# KMO_IO_MV2.net
KiCad netlist of a schematic drawn in EAGLE
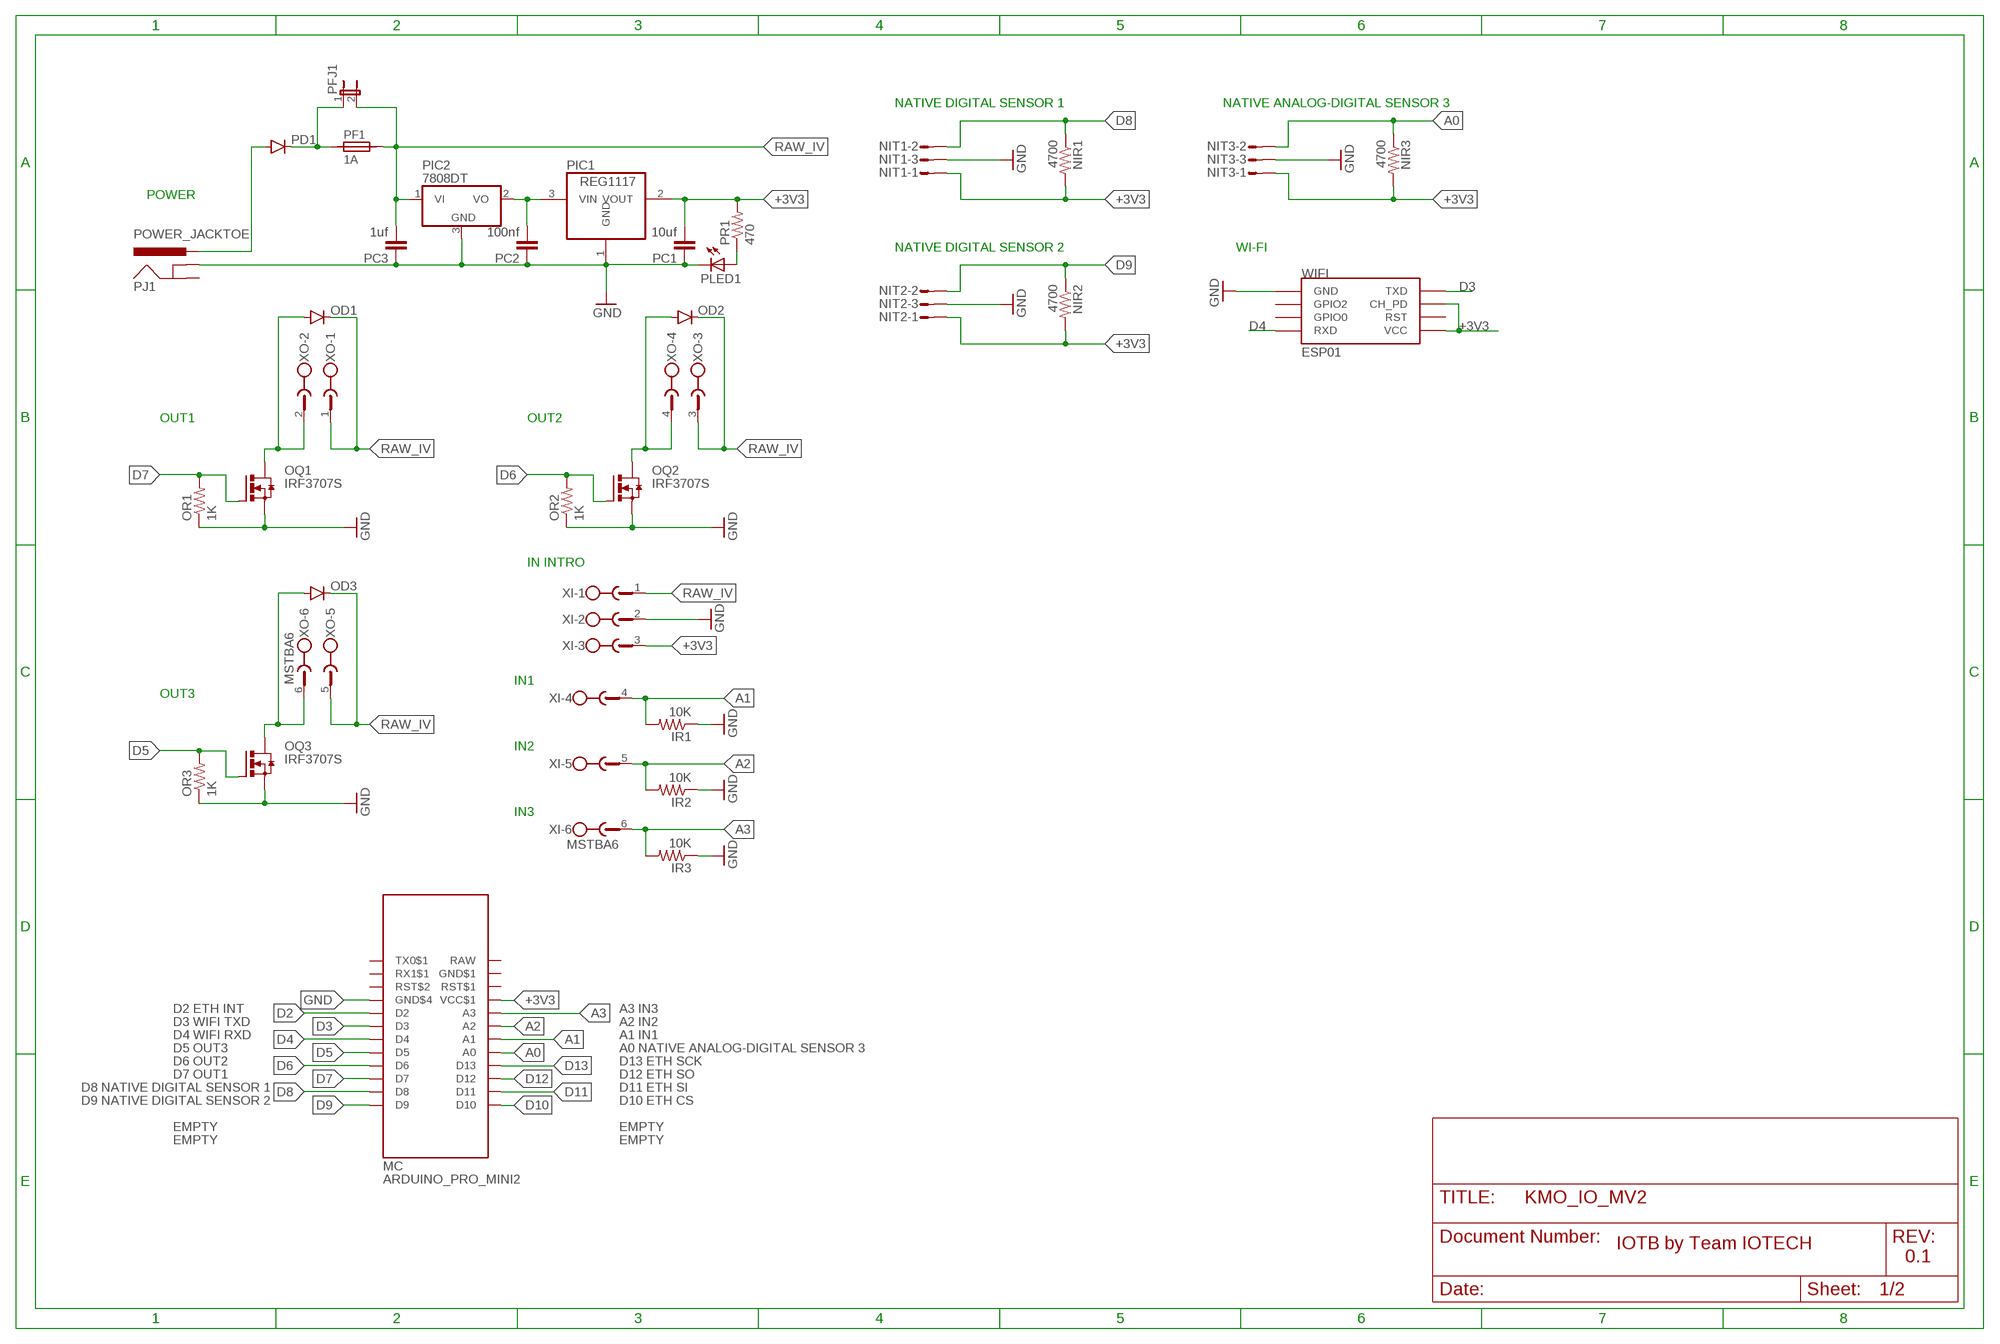
[diagram p0: schematic, sheet 1]
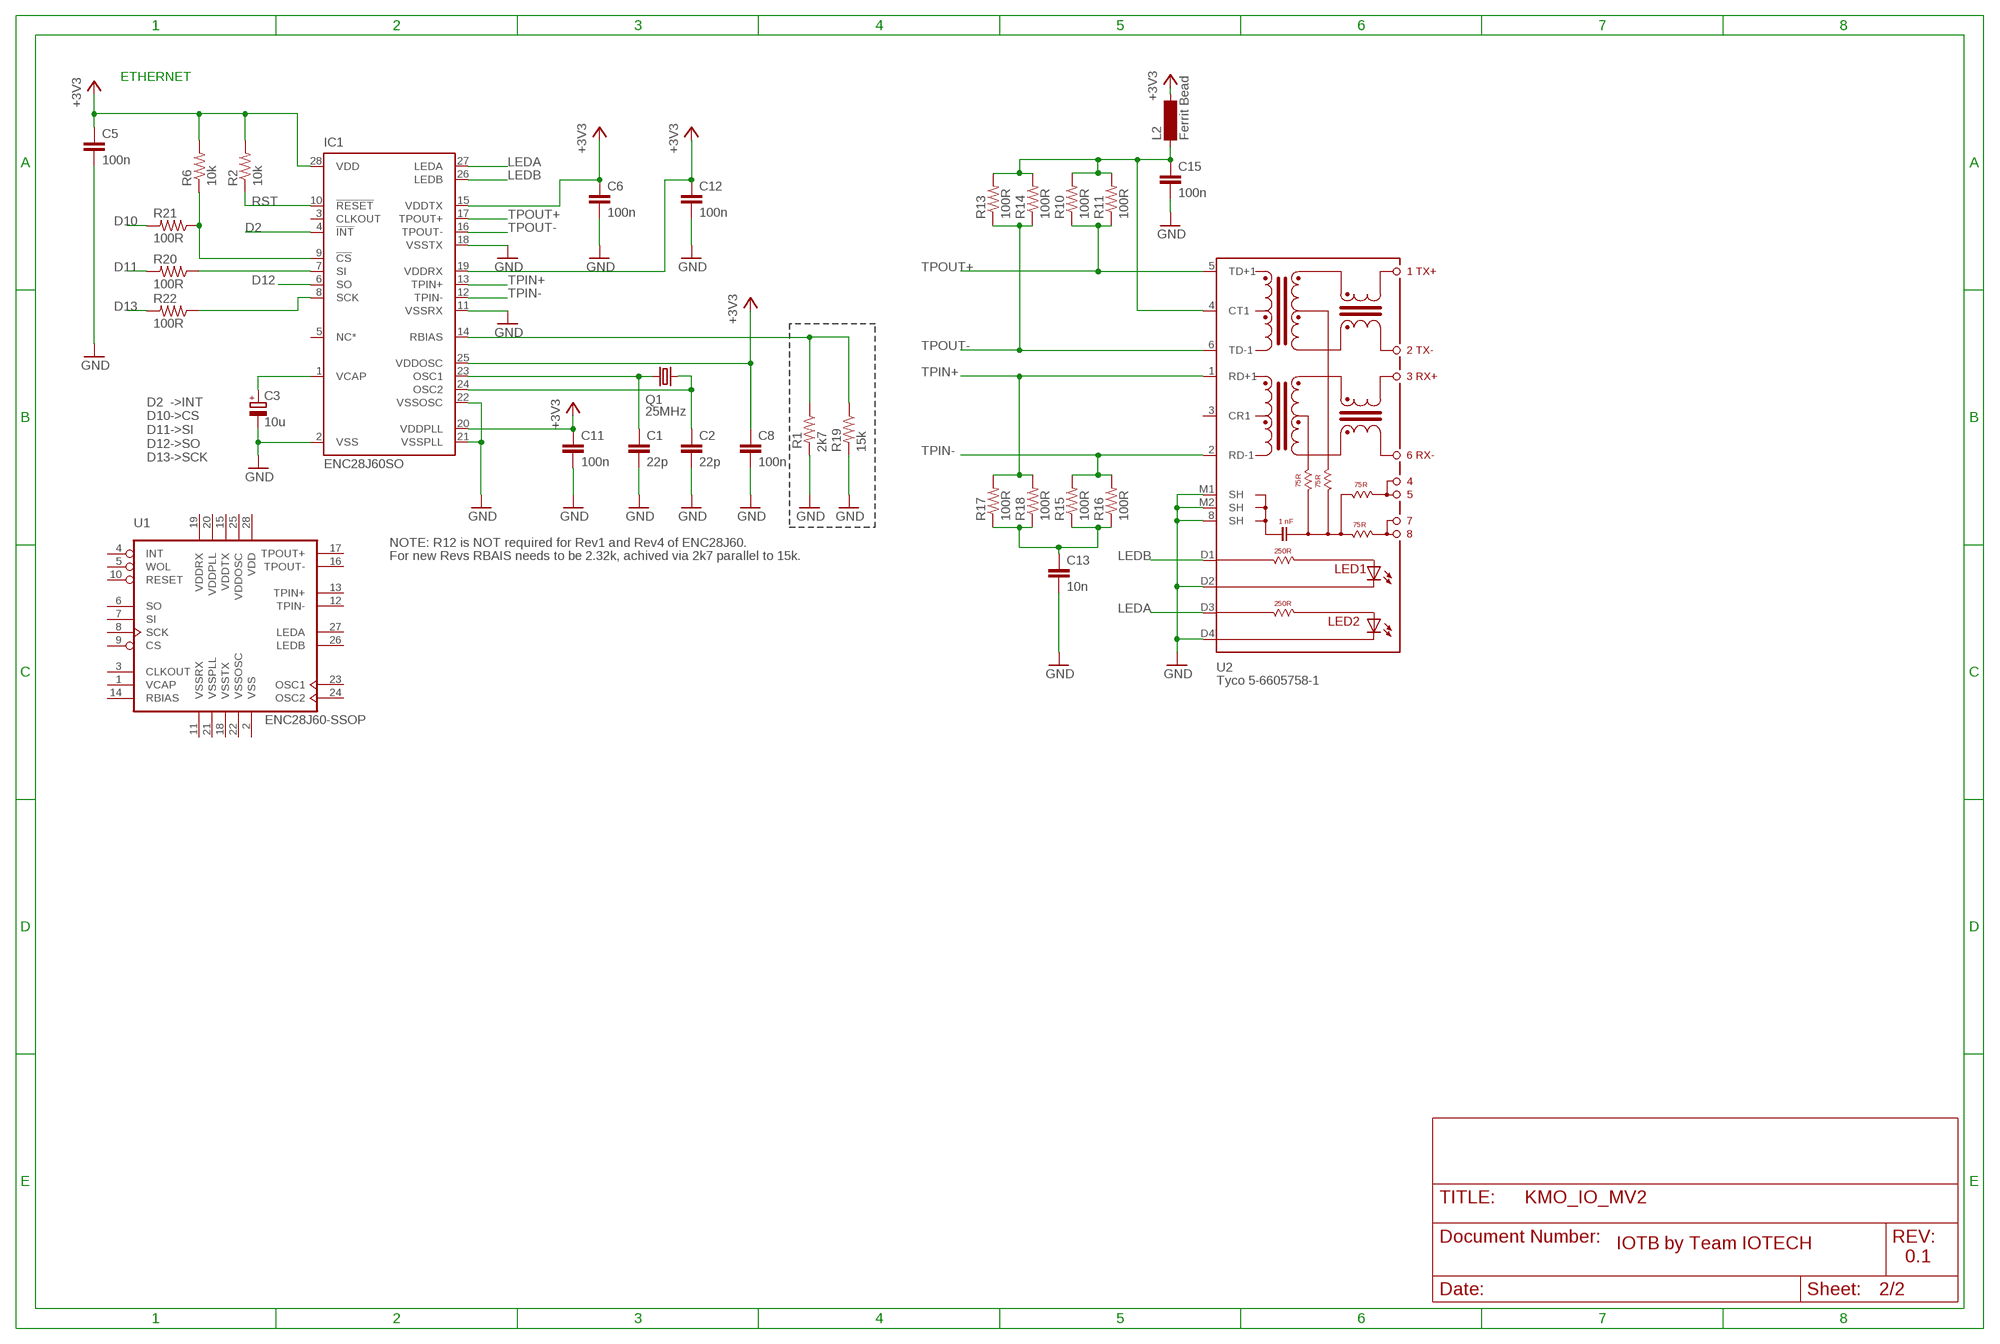
[diagram p1: schematic, sheet 2]

(export (version "E")
  (design (tool "Eeschema 10.0.6"))
  (components
    (comp (ref "C1")
      (value "22p")
      (footprint "eagle-import:0805")
      (libsource (lib "eagle-import") (part "SparkFun-Passives_CAP0805"))
    )
    (comp (ref "C2")
      (value "22p")
      (footprint "eagle-import:0805")
      (libsource (lib "eagle-import") (part "SparkFun-Passives_CAP0805"))
    )
    (comp (ref "C3")
      (value "10u")
      (footprint "eagle-import:E2,5-5")
      (libsource (lib "eagle-import") (part "CPOL-EUE2.5-5"))
    )
    (comp (ref "C5")
      (value "100n")
      (footprint "eagle-import:0805")
      (libsource (lib "eagle-import") (part "SparkFun-Passives_CAP0805"))
    )
    (comp (ref "C6")
      (value "100n")
      (footprint "eagle-import:0805")
      (libsource (lib "eagle-import") (part "SparkFun-Passives_CAP0805"))
    )
    (comp (ref "C8")
      (value "100n")
      (footprint "eagle-import:0805")
      (libsource (lib "eagle-import") (part "SparkFun-Passives_CAP0805"))
    )
    (comp (ref "C11")
      (value "100n")
      (footprint "eagle-import:0805")
      (libsource (lib "eagle-import") (part "SparkFun-Passives_CAP0805"))
    )
    (comp (ref "C12")
      (value "100n")
      (footprint "eagle-import:0805")
      (libsource (lib "eagle-import") (part "SparkFun-Passives_CAP0805"))
    )
    (comp (ref "C13")
      (value "10n")
      (footprint "eagle-import:0805")
      (libsource (lib "eagle-import") (part "SparkFun-Passives_CAP0805"))
    )
    (comp (ref "C15")
      (value "100n")
      (footprint "eagle-import:0805")
      (libsource (lib "eagle-import") (part "SparkFun-Passives_CAP0805"))
    )
    (comp (ref "IC1")
      (value "ENC28J60SO")
      (footprint "eagle-import:SO28W")
      (libsource (lib "eagle-import") (part "ENC28J60SO"))
    )
    (comp (ref "L2")
      (value "Ferrit Bead")
      (footprint "eagle-import:SM-1206")
      (libsource (lib "eagle-import") (part "SM-1206"))
    )
    (comp (ref "Q1")
      (value "25MHz")
      (footprint "eagle-import:HC49_S")
      (libsource (lib "eagle-import") (part "CRYSTALHC49S"))
    )
    (comp (ref "R1")
      (value "2k7")
      (footprint "eagle-import:0805")
      (libsource (lib "eagle-import") (part "RESISTOR0805-RES"))
    )
    (comp (ref "R2")
      (value "10k")
      (footprint "eagle-import:0805")
      (libsource (lib "eagle-import") (part "RESISTOR0805-RES"))
    )
    (comp (ref "R6")
      (value "10k")
      (footprint "eagle-import:0805")
      (libsource (lib "eagle-import") (part "RESISTOR0805-RES"))
    )
    (comp (ref "R10")
      (value "100R")
      (footprint "eagle-import:0805")
      (libsource (lib "eagle-import") (part "RESISTOR0805-RES"))
    )
    (comp (ref "R11")
      (value "100R")
      (footprint "eagle-import:0805")
      (libsource (lib "eagle-import") (part "RESISTOR0805-RES"))
    )
    (comp (ref "R13")
      (value "100R")
      (footprint "eagle-import:0805")
      (libsource (lib "eagle-import") (part "RESISTOR0805-RES"))
    )
    (comp (ref "R14")
      (value "100R")
      (footprint "eagle-import:0805")
      (libsource (lib "eagle-import") (part "RESISTOR0805-RES"))
    )
    (comp (ref "R15")
      (value "100R")
      (footprint "eagle-import:0805")
      (libsource (lib "eagle-import") (part "RESISTOR0805-RES"))
    )
    (comp (ref "R16")
      (value "100R")
      (footprint "eagle-import:0805")
      (libsource (lib "eagle-import") (part "RESISTOR0805-RES"))
    )
    (comp (ref "R17")
      (value "100R")
      (footprint "eagle-import:0805")
      (libsource (lib "eagle-import") (part "RESISTOR0805-RES"))
    )
    (comp (ref "R18")
      (value "100R")
      (footprint "eagle-import:0805")
      (libsource (lib "eagle-import") (part "RESISTOR0805-RES"))
    )
    (comp (ref "R19")
      (value "15k")
      (footprint "eagle-import:0805")
      (libsource (lib "eagle-import") (part "RESISTOR0805-RES"))
    )
    (comp (ref "R20")
      (value "100R")
      (footprint "eagle-import:0805")
      (libsource (lib "eagle-import") (part "RESISTOR0805-RES"))
    )
    (comp (ref "R21")
      (value "100R")
      (footprint "eagle-import:0805")
      (libsource (lib "eagle-import") (part "RESISTOR0805-RES"))
    )
    (comp (ref "R22")
      (value "100R")
      (footprint "eagle-import:0805")
      (libsource (lib "eagle-import") (part "RESISTOR0805-RES"))
    )
    (comp (ref "U1")
      (value "ENC28J60-SSOP")
      (footprint "eagle-import:SSOP28")
      (libsource (lib "eagle-import") (part "ENC28J60-SSOP"))
    )
    (comp (ref "U2")
      (value "Tyco 5-6605758-1")
      (footprint "eagle-import:5-6605758-1")
      (libsource (lib "eagle-import") (part "5-6605758-1"))
    )
    (comp (ref "IR1")
      (value "10K")
      (footprint "eagle-import:0805")
      (libsource (lib "eagle-import") (part "RESISTOR0805-RES"))
    )
    (comp (ref "IR2")
      (value "10K")
      (footprint "eagle-import:0805")
      (libsource (lib "eagle-import") (part "RESISTOR0805-RES"))
    )
    (comp (ref "IR3")
      (value "10K")
      (footprint "eagle-import:0805")
      (libsource (lib "eagle-import") (part "RESISTOR0805-RES"))
    )
    (comp (ref "MC")
      (value "ARDUINO_PRO_MINI2")
      (footprint "eagle-import:ARDUINO_PRO_MINI2")
      (libsource (lib "eagle-import") (part "ARDUINO_PRO_MINI2"))
    )
    (comp (ref "NIR1")
      (value "4700")
      (footprint "eagle-import:0805")
      (libsource (lib "eagle-import") (part "RESISTOR0805-RES"))
    )
    (comp (ref "NIR2")
      (value "4700")
      (footprint "eagle-import:0805")
      (libsource (lib "eagle-import") (part "RESISTOR0805-RES"))
    )
    (comp (ref "NIR3")
      (value "4700")
      (footprint "eagle-import:0805")
      (libsource (lib "eagle-import") (part "RESISTOR0805-RES"))
    )
    (comp (ref "NIT1")
      (value "S03P")
      (footprint "eagle-import:S03P")
      (libsource (lib "eagle-import") (part "S03P"))
    )
    (comp (ref "NIT2")
      (value "S03P")
      (footprint "eagle-import:S03P")
      (libsource (lib "eagle-import") (part "S03P"))
    )
    (comp (ref "NIT3")
      (value "S03P")
      (footprint "eagle-import:S03P")
      (libsource (lib "eagle-import") (part "S03P"))
    )
    (comp (ref "OD1")
      (value "DIODESMA")
      (footprint "eagle-import:SMA-DIODE")
      (libsource (lib "eagle-import") (part "DIODESMA"))
    )
    (comp (ref "OD2")
      (value "DIODESMA")
      (footprint "eagle-import:SMA-DIODE")
      (libsource (lib "eagle-import") (part "DIODESMA"))
    )
    (comp (ref "OD3")
      (value "DIODESMA")
      (footprint "eagle-import:SMA-DIODE")
      (libsource (lib "eagle-import") (part "DIODESMA"))
    )
    (comp (ref "OQ1")
      (value "IRF3707S")
      (footprint "eagle-import:D2PACK")
      (libsource (lib "eagle-import") (part "IRF3704S"))
    )
    (comp (ref "OQ2")
      (value "IRF3707S")
      (footprint "eagle-import:D2PACK")
      (libsource (lib "eagle-import") (part "IRF3704S"))
    )
    (comp (ref "OQ3")
      (value "IRF3707S")
      (footprint "eagle-import:D2PACK")
      (libsource (lib "eagle-import") (part "IRF3704S"))
    )
    (comp (ref "OR1")
      (value "1K")
      (footprint "eagle-import:0805")
      (libsource (lib "eagle-import") (part "RESISTOR0805-RES"))
    )
    (comp (ref "OR2")
      (value "1K")
      (footprint "eagle-import:0805")
      (libsource (lib "eagle-import") (part "RESISTOR0805-RES"))
    )
    (comp (ref "OR3")
      (value "1K")
      (footprint "eagle-import:0805")
      (libsource (lib "eagle-import") (part "RESISTOR0805-RES"))
    )
    (comp (ref "PC1")
      (value "10uf")
      (footprint "eagle-import:0805")
      (libsource (lib "eagle-import") (part "CAP0805"))
    )
    (comp (ref "PC2")
      (value "100nf")
      (footprint "eagle-import:0805")
      (libsource (lib "eagle-import") (part "CAP0805"))
    )
    (comp (ref "PC3")
      (value "1uf")
      (footprint "eagle-import:0805")
      (libsource (lib "eagle-import") (part "CAP0805"))
    )
    (comp (ref "PD1")
      (value "DIODESMA")
      (footprint "eagle-import:SMA-DIODE")
      (libsource (lib "eagle-import") (part "DIODESMA"))
    )
    (comp (ref "PF1")
      (value "1A")
      (footprint "eagle-import:1820")
      (libsource (lib "eagle-import") (part "SIBA194600"))
    )
    (comp (ref "PFJ1")
      (value "JP1E")
      (footprint "eagle-import:JP1")
      (libsource (lib "eagle-import") (part "JP1E"))
    )
    (comp (ref "PIC1")
      (value "REG1117")
      (footprint "eagle-import:SOT223")
      (libsource (lib "eagle-import") (part "REG1117"))
    )
    (comp (ref "PIC2")
      (value "7808DT")
      (footprint "eagle-import:TO252")
      (libsource (lib "eagle-import") (part "78DT08"))
    )
    (comp (ref "PJ1")
      (value "POWER_JACKTOE")
      (footprint "eagle-import:POWER_JACK_SMD_OVERPASTE_TOE")
      (libsource (lib "eagle-import") (part "POWER_JACKTOE"))
    )
    (comp (ref "PLED1")
      (value "LEDCHIP-LED0805")
      (footprint "eagle-import:CHIP-LED0805")
      (libsource (lib "eagle-import") (part "LEDCHIP-LED0805"))
    )
    (comp (ref "PR1")
      (value "470")
      (footprint "eagle-import:0805")
      (libsource (lib "eagle-import") (part "RESISTOR0805-RES"))
    )
    (comp (ref "WIFI")
      (value "ESP01")
      (footprint "eagle-import:ESP01")
      (libsource (lib "eagle-import") (part "ESP01"))
    )
    (comp (ref "XI")
      (value "MSTBA6")
      (footprint "eagle-import:MSTBA6")
      (fields (field (name "MF") "FARNELL") (field (name "MPN") "1757284"))
      (libsource (lib "eagle-import") (part "MSTBA6"))
    )
    (comp (ref "XO")
      (value "MSTBA6")
      (footprint "eagle-import:MSTBA6")
      (fields (field (name "MF") "FARNELL") (field (name "MPN") "1757284"))
      (libsource (lib "eagle-import") (part "MSTBA6"))
    )
  )
  (nets
    (net (code "1") (name "+3V3") (class "Default")
      (node (ref "C11") (pin "1") (pinfunction "1_1") (pintype "passive"))
      (node (ref "C12") (pin "1") (pinfunction "1_1") (pintype "passive"))
      (node (ref "C5") (pin "1") (pinfunction "1_1") (pintype "passive"))
      (node (ref "C6") (pin "1") (pinfunction "1_1") (pintype "passive"))
      (node (ref "C8") (pin "1") (pinfunction "1_1") (pintype "passive"))
      (node (ref "IC1") (pin "15") (pinfunction "VDDTX_15") (pintype "input"))
      (node (ref "IC1") (pin "19") (pinfunction "VDDRX_19") (pintype "input"))
      (node (ref "IC1") (pin "20") (pinfunction "VDDPLL_20") (pintype "input"))
      (node (ref "IC1") (pin "25") (pinfunction "VDDOSC_25") (pintype "input"))
      (node (ref "IC1") (pin "28") (pinfunction "VDD_28") (pintype "input"))
      (node (ref "L2") (pin "2") (pinfunction "2_2") (pintype "passive"))
      (node (ref "MC") (pin "VCC$1") (pinfunction "VCC$1_VCC$1") (pintype "power_in"))
      (node (ref "NIR1") (pin "2") (pinfunction "2_2") (pintype "passive"))
      (node (ref "NIR2") (pin "2") (pinfunction "2_2") (pintype "passive"))
      (node (ref "NIR3") (pin "2") (pinfunction "2_2") (pintype "passive"))
      (node (ref "NIT1") (pin "1") (pinfunction "S_1") (pintype "passive"))
      (node (ref "NIT2") (pin "1") (pinfunction "S_1") (pintype "passive"))
      (node (ref "NIT3") (pin "1") (pinfunction "S_1") (pintype "passive"))
      (node (ref "PC1") (pin "2") (pinfunction "2_2") (pintype "passive"))
      (node (ref "PIC1") (pin "2") (pinfunction "VOUT_2") (pintype "output"))
      (node (ref "PR1") (pin "2") (pinfunction "2_2") (pintype "passive"))
      (node (ref "R2") (pin "2") (pinfunction "2_2") (pintype "passive"))
      (node (ref "R6") (pin "2") (pinfunction "2_2") (pintype "passive"))
      (node (ref "WIFI") (pin "CH_PD") (pinfunction "CH_PD_CH_PD") (pintype "bidirectional"))
      (node (ref "WIFI") (pin "VCC") (pinfunction "VCC_VCC") (pintype "bidirectional"))
      (node (ref "XI") (pin "3") (pinfunction "1_3") (pintype "passive"))
    )
    (net (code "2") (name "A0") (class "Default")
      (node (ref "MC") (pin "A0") (pinfunction "A0_A0") (pintype "bidirectional"))
      (node (ref "NIR3") (pin "1") (pinfunction "1_1") (pintype "passive"))
      (node (ref "NIT3") (pin "2") (pinfunction "S_2") (pintype "passive"))
    )
    (net (code "3") (name "A1") (class "Default")
      (node (ref "IR1") (pin "2") (pinfunction "2_2") (pintype "passive"))
      (node (ref "MC") (pin "A1") (pinfunction "A1_A1") (pintype "bidirectional"))
      (node (ref "XI") (pin "4") (pinfunction "1_4") (pintype "passive"))
    )
    (net (code "4") (name "A2") (class "Default")
      (node (ref "IR2") (pin "2") (pinfunction "2_2") (pintype "passive"))
      (node (ref "MC") (pin "A2") (pinfunction "A2_A2") (pintype "bidirectional"))
      (node (ref "XI") (pin "5") (pinfunction "1_5") (pintype "passive"))
    )
    (net (code "5") (name "A3") (class "Default")
      (node (ref "IR3") (pin "2") (pinfunction "2_2") (pintype "passive"))
      (node (ref "MC") (pin "A3") (pinfunction "A3_A3") (pintype "bidirectional"))
      (node (ref "XI") (pin "6") (pinfunction "1_6") (pintype "passive"))
    )
    (net (code "6") (name "D2") (class "Default")
      (node (ref "IC1") (pin "4") (pinfunction "~{INT}_4") (pintype "output"))
      (node (ref "MC") (pin "D2") (pinfunction "D2_D2") (pintype "bidirectional"))
    )
    (net (code "7") (name "D3") (class "Default")
      (node (ref "MC") (pin "D3") (pinfunction "D3_D3") (pintype "bidirectional"))
      (node (ref "WIFI") (pin "TX") (pinfunction "TXD_TX") (pintype "bidirectional"))
    )
    (net (code "8") (name "D4") (class "Default")
      (node (ref "MC") (pin "D4") (pinfunction "D4_D4") (pintype "bidirectional"))
      (node (ref "WIFI") (pin "RX") (pinfunction "RXD_RX") (pintype "bidirectional"))
    )
    (net (code "9") (name "D5") (class "Default")
      (node (ref "MC") (pin "D5") (pinfunction "D5_D5") (pintype "bidirectional"))
      (node (ref "OQ3") (pin "1") (pinfunction "G_1") (pintype "passive"))
      (node (ref "OR3") (pin "2") (pinfunction "2_2") (pintype "passive"))
    )
    (net (code "10") (name "D6") (class "Default")
      (node (ref "MC") (pin "D6") (pinfunction "D6_D6") (pintype "bidirectional"))
      (node (ref "OQ2") (pin "1") (pinfunction "G_1") (pintype "passive"))
      (node (ref "OR2") (pin "2") (pinfunction "2_2") (pintype "passive"))
    )
    (net (code "11") (name "D7") (class "Default")
      (node (ref "MC") (pin "D7") (pinfunction "D7_D7") (pintype "bidirectional"))
      (node (ref "OQ1") (pin "1") (pinfunction "G_1") (pintype "passive"))
      (node (ref "OR1") (pin "2") (pinfunction "2_2") (pintype "passive"))
    )
    (net (code "12") (name "D8") (class "Default")
      (node (ref "MC") (pin "D8") (pinfunction "D8_D8") (pintype "bidirectional"))
      (node (ref "NIR1") (pin "1") (pinfunction "1_1") (pintype "passive"))
      (node (ref "NIT1") (pin "2") (pinfunction "S_2") (pintype "passive"))
    )
    (net (code "13") (name "D9") (class "Default")
      (node (ref "MC") (pin "D9") (pinfunction "D9_D9") (pintype "bidirectional"))
      (node (ref "NIR2") (pin "1") (pinfunction "1_1") (pintype "passive"))
      (node (ref "NIT2") (pin "2") (pinfunction "S_2") (pintype "passive"))
    )
    (net (code "14") (name "D10") (class "Default")
      (node (ref "MC") (pin "D10") (pinfunction "D10_D10") (pintype "bidirectional"))
      (node (ref "R21") (pin "2") (pinfunction "2_2") (pintype "passive"))
    )
    (net (code "15") (name "D11") (class "Default")
      (node (ref "MC") (pin "D11") (pinfunction "D11_D11") (pintype "bidirectional"))
      (node (ref "R20") (pin "2") (pinfunction "2_2") (pintype "passive"))
    )
    (net (code "16") (name "D12") (class "Default")
      (node (ref "IC1") (pin "6") (pinfunction "SO_6") (pintype "output"))
      (node (ref "MC") (pin "D12") (pinfunction "D12_D12") (pintype "bidirectional"))
    )
    (net (code "17") (name "D13") (class "Default")
      (node (ref "MC") (pin "D13") (pinfunction "D13_D13") (pintype "bidirectional"))
      (node (ref "R22") (pin "2") (pinfunction "2_2") (pintype "passive"))
    )
    (net (code "18") (name "GND") (class "Default")
      (node (ref "C1") (pin "2") (pinfunction "2_2") (pintype "passive"))
      (node (ref "C11") (pin "2") (pinfunction "2_2") (pintype "passive"))
      (node (ref "C12") (pin "2") (pinfunction "2_2") (pintype "passive"))
      (node (ref "C13") (pin "2") (pinfunction "2_2") (pintype "passive"))
      (node (ref "C15") (pin "2") (pinfunction "2_2") (pintype "passive"))
      (node (ref "C2") (pin "2") (pinfunction "2_2") (pintype "passive"))
      (node (ref "C3") (pin "-") (pinfunction "-_-") (pintype "passive"))
      (node (ref "C5") (pin "2") (pinfunction "2_2") (pintype "passive"))
      (node (ref "C6") (pin "2") (pinfunction "2_2") (pintype "passive"))
      (node (ref "C8") (pin "2") (pinfunction "2_2") (pintype "passive"))
      (node (ref "IC1") (pin "11") (pinfunction "VSSRX_11") (pintype "input"))
      (node (ref "IC1") (pin "18") (pinfunction "VSSTX_18") (pintype "input"))
      (node (ref "IC1") (pin "2") (pinfunction "VSS_2") (pintype "input"))
      (node (ref "IC1") (pin "21") (pinfunction "VSSPLL_21") (pintype "input"))
      (node (ref "IC1") (pin "22") (pinfunction "VSSOSC_22") (pintype "input"))
      (node (ref "IR1") (pin "1") (pinfunction "1_1") (pintype "passive"))
      (node (ref "IR2") (pin "1") (pinfunction "1_1") (pintype "passive"))
      (node (ref "IR3") (pin "1") (pinfunction "1_1") (pintype "passive"))
      (node (ref "MC") (pin "GND$4") (pinfunction "GND$4_GND$4") (pintype "power_in"))
      (node (ref "NIT1") (pin "3") (pinfunction "S_3") (pintype "passive"))
      (node (ref "NIT2") (pin "3") (pinfunction "S_3") (pintype "passive"))
      (node (ref "NIT3") (pin "3") (pinfunction "S_3") (pintype "passive"))
      (node (ref "OQ1") (pin "3") (pinfunction "S_3") (pintype "passive"))
      (node (ref "OQ2") (pin "3") (pinfunction "S_3") (pintype "passive"))
      (node (ref "OQ3") (pin "3") (pinfunction "S_3") (pintype "passive"))
      (node (ref "OR1") (pin "1") (pinfunction "1_1") (pintype "passive"))
      (node (ref "OR2") (pin "1") (pinfunction "1_1") (pintype "passive"))
      (node (ref "OR3") (pin "1") (pinfunction "1_1") (pintype "passive"))
      (node (ref "PC1") (pin "1") (pinfunction "1_1") (pintype "passive"))
      (node (ref "PC2") (pin "1") (pinfunction "1_1") (pintype "passive"))
      (node (ref "PC3") (pin "1") (pinfunction "1_1") (pintype "passive"))
      (node (ref "PIC1") (pin "1") (pinfunction "GND_1") (pintype "power_in"))
      (node (ref "PIC2") (pin "3") (pinfunction "GND_3") (pintype "passive"))
      (node (ref "PJ1") (pin "GND") (pinfunction "GNDBREAK_GND") (pintype "bidirectional"))
      (node (ref "PLED1") (pin "C") (pinfunction "C_C") (pintype "passive"))
      (node (ref "R1") (pin "2") (pinfunction "2_2") (pintype "passive"))
      (node (ref "R19") (pin "2") (pinfunction "2_2") (pintype "passive"))
      (node (ref "U2") (pin "8") (pinfunction "SH_8") (pintype "input"))
      (node (ref "U2") (pin "D2") (pinfunction "D2_D2") (pintype "input"))
      (node (ref "U2") (pin "D4") (pinfunction "D4_D4") (pintype "input"))
      (node (ref "U2") (pin "M1") (pinfunction "SH_M1") (pintype "input"))
      (node (ref "U2") (pin "M2") (pinfunction "SH_M2") (pintype "input"))
      (node (ref "WIFI") (pin "GND") (pinfunction "GND_GND") (pintype "bidirectional"))
      (node (ref "XI") (pin "2") (pinfunction "1_2") (pintype "passive"))
    )
    (net (code "19") (name "GND$1") (class "Default")
      (node (ref "MC") (pin "GDN$1") (pinfunction "GND$1_GDN$1") (pintype "power_in"))
    )
    (net (code "20") (name "LEDA") (class "Default")
      (node (ref "IC1") (pin "27") (pinfunction "LEDA_27") (pintype "output"))
      (node (ref "U2") (pin "D3") (pinfunction "D3_D3") (pintype "input"))
    )
    (net (code "21") (name "LEDB") (class "Default")
      (node (ref "IC1") (pin "26") (pinfunction "LEDB_26") (pintype "output"))
      (node (ref "U2") (pin "D1") (pinfunction "D1_D1") (pintype "input"))
    )
    (net (code "22") (name "Net-(C13-Pad1)") (class "Default")
      (node (ref "C13") (pin "1") (pinfunction "1_1") (pintype "passive"))
      (node (ref "R15") (pin "1") (pinfunction "1_1") (pintype "passive"))
      (node (ref "R16") (pin "1") (pinfunction "1_1") (pintype "passive"))
      (node (ref "R17") (pin "1") (pinfunction "1_1") (pintype "passive"))
      (node (ref "R18") (pin "1") (pinfunction "1_1") (pintype "passive"))
    )
    (net (code "23") (name "Net-(IC1-OSC1)") (class "Default")
      (node (ref "C1") (pin "1") (pinfunction "1_1") (pintype "passive"))
      (node (ref "IC1") (pin "23") (pinfunction "OSC1_23") (pintype "input"))
      (node (ref "Q1") (pin "1") (pinfunction "1_1") (pintype "passive"))
    )
    (net (code "24") (name "Net-(IC1-OSC2)") (class "Default")
      (node (ref "C2") (pin "1") (pinfunction "1_1") (pintype "passive"))
      (node (ref "IC1") (pin "24") (pinfunction "OSC2_24") (pintype "output"))
      (node (ref "Q1") (pin "2") (pinfunction "2_2") (pintype "passive"))
    )
    (net (code "25") (name "Net-(IC1-RBIAS)") (class "Default")
      (node (ref "IC1") (pin "14") (pinfunction "RBIAS_14") (pintype "input"))
      (node (ref "R1") (pin "1") (pinfunction "1_1") (pintype "passive"))
      (node (ref "R19") (pin "1") (pinfunction "1_1") (pintype "passive"))
    )
    (net (code "26") (name "Net-(IC1-SCK)") (class "Default")
      (node (ref "IC1") (pin "8") (pinfunction "SCK_8") (pintype "input"))
      (node (ref "R22") (pin "1") (pinfunction "1_1") (pintype "passive"))
    )
    (net (code "27") (name "Net-(IC1-SI)") (class "Default")
      (node (ref "IC1") (pin "7") (pinfunction "SI_7") (pintype "input"))
      (node (ref "R20") (pin "1") (pinfunction "1_1") (pintype "passive"))
    )
    (net (code "28") (name "Net-(IC1-VCAP)") (class "Default")
      (node (ref "C3") (pin "+") (pinfunction "+_+") (pintype "passive"))
      (node (ref "IC1") (pin "1") (pinfunction "VCAP_1") (pintype "input"))
    )
    (net (code "29") (name "Net-(IC1-~{CS})") (class "Default")
      (node (ref "IC1") (pin "9") (pinfunction "~{CS}_9") (pintype "input"))
      (node (ref "R21") (pin "1") (pinfunction "1_1") (pintype "passive"))
      (node (ref "R6") (pin "1") (pinfunction "1_1") (pintype "passive"))
    )
    (net (code "30") (name "Net-(OQ1-D)") (class "Default")
      (node (ref "OD1") (pin "A") (pinfunction "A_A") (pintype "passive"))
      (node (ref "OQ1") (pin "2") (pinfunction "D_2") (pintype "passive"))
      (node (ref "XO") (pin "2") (pinfunction "1_2") (pintype "passive"))
    )
    (net (code "31") (name "Net-(OQ2-D)") (class "Default")
      (node (ref "OD2") (pin "A") (pinfunction "A_A") (pintype "passive"))
      (node (ref "OQ2") (pin "2") (pinfunction "D_2") (pintype "passive"))
      (node (ref "XO") (pin "4") (pinfunction "1_4") (pintype "passive"))
    )
    (net (code "32") (name "Net-(OQ3-D)") (class "Default")
      (node (ref "OD3") (pin "A") (pinfunction "A_A") (pintype "passive"))
      (node (ref "OQ3") (pin "2") (pinfunction "D_2") (pintype "passive"))
      (node (ref "XO") (pin "6") (pinfunction "1_6") (pintype "passive"))
    )
    (net (code "33") (name "Net-(PD1-PadC)") (class "Default")
      (node (ref "PD1") (pin "C") (pinfunction "C_C") (pintype "passive"))
      (node (ref "PF1") (pin "1") (pinfunction "1_1") (pintype "passive"))
      (node (ref "PFJ1") (pin "1") (pinfunction "1_1") (pintype "passive"))
    )
    (net (code "34") (name "Net-(PIC1-VIN)") (class "Default")
      (node (ref "PC2") (pin "2") (pinfunction "2_2") (pintype "passive"))
      (node (ref "PIC1") (pin "3") (pinfunction "VIN_3") (pintype "input"))
      (node (ref "PIC2") (pin "2") (pinfunction "VO_2") (pintype "passive"))
    )
    (net (code "35") (name "Net-(PJ1-PWR)") (class "Default")
      (node (ref "PD1") (pin "A") (pinfunction "A_A") (pintype "passive"))
      (node (ref "PJ1") (pin "VIN0") (pinfunction "PWR_VIN0") (pintype "bidirectional"))
    )
    (net (code "36") (name "Net-(PLED1-PadA)") (class "Default")
      (node (ref "PLED1") (pin "A") (pinfunction "A_A") (pintype "passive"))
      (node (ref "PR1") (pin "1") (pinfunction "1_1") (pintype "passive"))
    )
    (net (code "37") (name "Net-(U2-CT1)") (class "Default")
      (node (ref "C15") (pin "1") (pinfunction "1_1") (pintype "passive"))
      (node (ref "L2") (pin "1") (pinfunction "1_1") (pintype "passive"))
      (node (ref "R10") (pin "2") (pinfunction "2_2") (pintype "passive"))
      (node (ref "R11") (pin "2") (pinfunction "2_2") (pintype "passive"))
      (node (ref "R13") (pin "2") (pinfunction "2_2") (pintype "passive"))
      (node (ref "R14") (pin "2") (pinfunction "2_2") (pintype "passive"))
      (node (ref "U2") (pin "4") (pinfunction "CT1_4") (pintype "input"))
    )
    (net (code "38") (name "RAW") (class "Default")
      (node (ref "MC") (pin "RAW") (pinfunction "RAW_RAW") (pintype "power_in"))
    )
    (net (code "39") (name "RAW_IV") (class "Default")
      (node (ref "OD1") (pin "C") (pinfunction "C_C") (pintype "passive"))
      (node (ref "OD2") (pin "C") (pinfunction "C_C") (pintype "passive"))
      (node (ref "OD3") (pin "C") (pinfunction "C_C") (pintype "passive"))
      (node (ref "PC3") (pin "2") (pinfunction "2_2") (pintype "passive"))
      (node (ref "PF1") (pin "2") (pinfunction "2_2") (pintype "passive"))
      (node (ref "PFJ1") (pin "2") (pinfunction "2_2") (pintype "passive"))
      (node (ref "PIC2") (pin "1") (pinfunction "VI_1") (pintype "input"))
      (node (ref "XI") (pin "1") (pinfunction "1_1") (pintype "passive"))
      (node (ref "XO") (pin "1") (pinfunction "1_1") (pintype "passive"))
      (node (ref "XO") (pin "3") (pinfunction "1_3") (pintype "passive"))
      (node (ref "XO") (pin "5") (pinfunction "1_5") (pintype "passive"))
    )
    (net (code "40") (name "RST") (class "Default")
      (node (ref "IC1") (pin "10") (pinfunction "~{RESET}_10") (pintype "input"))
      (node (ref "R2") (pin "1") (pinfunction "1_1") (pintype "passive"))
    )
    (net (code "41") (name "TPIN+") (class "Default")
      (node (ref "IC1") (pin "13") (pinfunction "TPIN+_13") (pintype "input"))
      (node (ref "R17") (pin "2") (pinfunction "2_2") (pintype "passive"))
      (node (ref "R18") (pin "2") (pinfunction "2_2") (pintype "passive"))
      (node (ref "U2") (pin "1") (pinfunction "RD+1_1") (pintype "input"))
    )
    (net (code "42") (name "TPIN-") (class "Default")
      (node (ref "IC1") (pin "12") (pinfunction "TPIN-_12") (pintype "input"))
      (node (ref "R15") (pin "2") (pinfunction "2_2") (pintype "passive"))
      (node (ref "R16") (pin "2") (pinfunction "2_2") (pintype "passive"))
      (node (ref "U2") (pin "2") (pinfunction "RD-1_2") (pintype "input"))
    )
    (net (code "43") (name "TPOUT+") (class "Default")
      (node (ref "IC1") (pin "17") (pinfunction "TPOUT+_17") (pintype "output"))
      (node (ref "R10") (pin "1") (pinfunction "1_1") (pintype "passive"))
      (node (ref "R11") (pin "1") (pinfunction "1_1") (pintype "passive"))
      (node (ref "U2") (pin "5") (pinfunction "TD+1_5") (pintype "input"))
    )
    (net (code "44") (name "TPOUT-") (class "Default")
      (node (ref "IC1") (pin "16") (pinfunction "TPOUT-_16") (pintype "output"))
      (node (ref "R13") (pin "1") (pinfunction "1_1") (pintype "passive"))
      (node (ref "R14") (pin "1") (pinfunction "1_1") (pintype "passive"))
      (node (ref "U2") (pin "6") (pinfunction "TD-1_6") (pintype "input"))
    )
    (net (code "45") (name "VCAP") (class "Default")
      (node (ref "U1") (pin "1") (pinfunction "VCAP_1") (pintype "power_in"))
    )
    (net (code "46") (name "VDD") (class "Default")
      (node (ref "U1") (pin "28") (pinfunction "VDD_28") (pintype "power_in"))
    )
    (net (code "47") (name "VDDOSC") (class "Default")
      (node (ref "U1") (pin "25") (pinfunction "VDDOSC_25") (pintype "power_in"))
    )
    (net (code "48") (name "VDDPLL") (class "Default")
      (node (ref "U1") (pin "20") (pinfunction "VDDPLL_20") (pintype "power_in"))
    )
    (net (code "49") (name "VDDRX") (class "Default")
      (node (ref "U1") (pin "19") (pinfunction "VDDRX_19") (pintype "power_in"))
    )
    (net (code "50") (name "VDDTX") (class "Default")
      (node (ref "U1") (pin "15") (pinfunction "VDDTX_15") (pintype "power_in"))
    )
    (net (code "51") (name "VSS") (class "Default")
      (node (ref "U1") (pin "2") (pinfunction "VSS_2") (pintype "power_in"))
    )
    (net (code "52") (name "VSSOSC") (class "Default")
      (node (ref "U1") (pin "22") (pinfunction "VSSOSC_22") (pintype "power_in"))
    )
    (net (code "53") (name "VSSPLL") (class "Default")
      (node (ref "U1") (pin "21") (pinfunction "VSSPLL_21") (pintype "power_in"))
    )
    (net (code "54") (name "VSSRX") (class "Default")
      (node (ref "U1") (pin "11") (pinfunction "VSSRX_11") (pintype "power_in"))
    )
    (net (code "55") (name "VSSTX") (class "Default")
      (node (ref "U1") (pin "18") (pinfunction "VSSTX_18") (pintype "power_in"))
    )
    (net (code "56") (name "unconnected-(IC1-CLKOUT-Pad3)") (class "Default")
      (node (ref "IC1") (pin "3") (pinfunction "CLKOUT_3") (pintype "output"))
    )
    (net (code "57") (name "unconnected-(IC1-NC*-Pad5)") (class "Default")
      (node (ref "IC1") (pin "5") (pinfunction "NC*_5") (pintype "output"))
    )
    (net (code "58") (name "unconnected-(MC-PadRST$1)") (class "Default")
      (node (ref "MC") (pin "RST$1") (pinfunction "RST$1_RST$1") (pintype "input"))
    )
    (net (code "59") (name "unconnected-(MC-PadRST$2)") (class "Default")
      (node (ref "MC") (pin "RST$2") (pinfunction "RST$2_RST$2") (pintype "input"))
    )
    (net (code "60") (name "unconnected-(MC-PadRX1$1)") (class "Default")
      (node (ref "MC") (pin "RX1$1") (pinfunction "RX1$1_RX1$1") (pintype "bidirectional"))
    )
    (net (code "61") (name "unconnected-(MC-PadTX0$1)") (class "Default")
      (node (ref "MC") (pin "TX0$1") (pinfunction "TX0$1_TX0$1") (pintype "bidirectional"))
    )
    (net (code "62") (name "unconnected-(PJ1-GND-PadP$4)") (class "Default")
      (node (ref "PJ1") (pin "P$4") (pinfunction "GND_P$4") (pintype "bidirectional"))
    )
    (net (code "63") (name "unconnected-(U1-CLKOUT-Pad3)") (class "Default")
      (node (ref "U1") (pin "3") (pinfunction "CLKOUT_3") (pintype "output"))
    )
    (net (code "64") (name "unconnected-(U1-CS-Pad9)") (class "Default")
      (node (ref "U1") (pin "9") (pinfunction "CS_9") (pintype "input"))
    )
    (net (code "65") (name "unconnected-(U1-INT-Pad4)") (class "Default")
      (node (ref "U1") (pin "4") (pinfunction "INT_4") (pintype "output"))
    )
    (net (code "66") (name "unconnected-(U1-LEDA-Pad27)") (class "Default")
      (node (ref "U1") (pin "27") (pinfunction "LEDA_27") (pintype "output"))
    )
    (net (code "67") (name "unconnected-(U1-LEDB-Pad26)") (class "Default")
      (node (ref "U1") (pin "26") (pinfunction "LEDB_26") (pintype "output"))
    )
    (net (code "68") (name "unconnected-(U1-OSC1-Pad23)") (class "Default")
      (node (ref "U1") (pin "23") (pinfunction "OSC1_23") (pintype "input"))
    )
    (net (code "69") (name "unconnected-(U1-OSC2-Pad24)") (class "Default")
      (node (ref "U1") (pin "24") (pinfunction "OSC2_24") (pintype "output"))
    )
    (net (code "70") (name "unconnected-(U1-RBIAS-Pad14)") (class "Default")
      (node (ref "U1") (pin "14") (pinfunction "RBIAS_14") (pintype "passive"))
    )
    (net (code "71") (name "unconnected-(U1-RESET-Pad10)") (class "Default")
      (node (ref "U1") (pin "10") (pinfunction "RESET_10") (pintype "input"))
    )
    (net (code "72") (name "unconnected-(U1-SCK-Pad8)") (class "Default")
      (node (ref "U1") (pin "8") (pinfunction "SCK_8") (pintype "input"))
    )
    (net (code "73") (name "unconnected-(U1-SI-Pad7)") (class "Default")
      (node (ref "U1") (pin "7") (pinfunction "SI_7") (pintype "input"))
    )
    (net (code "74") (name "unconnected-(U1-SO-Pad6)") (class "Default")
      (node (ref "U1") (pin "6") (pinfunction "SO_6") (pintype "output"))
    )
    (net (code "75") (name "unconnected-(U1-TPIN+-Pad13)") (class "Default")
      (node (ref "U1") (pin "13") (pinfunction "TPIN+_13") (pintype "input"))
    )
    (net (code "76") (name "unconnected-(U1-TPIN--Pad12)") (class "Default")
      (node (ref "U1") (pin "12") (pinfunction "TPIN-_12") (pintype "input"))
    )
    (net (code "77") (name "unconnected-(U1-TPOUT+-Pad17)") (class "Default")
      (node (ref "U1") (pin "17") (pinfunction "TPOUT+_17") (pintype "output"))
    )
    (net (code "78") (name "unconnected-(U1-TPOUT--Pad16)") (class "Default")
      (node (ref "U1") (pin "16") (pinfunction "TPOUT-_16") (pintype "output"))
    )
    (net (code "79") (name "unconnected-(U1-WOL-Pad5)") (class "Default")
      (node (ref "U1") (pin "5") (pinfunction "WOL_5") (pintype "output"))
    )
    (net (code "80") (name "unconnected-(U2-CR1-Pad3)") (class "Default")
      (node (ref "U2") (pin "3") (pinfunction "CR1_3") (pintype "input"))
    )
    (net (code "81") (name "unconnected-(WIFI-PadGPIO0)") (class "Default")
      (node (ref "WIFI") (pin "GPIO0") (pinfunction "GPIO0_GPIO0") (pintype "bidirectional"))
    )
    (net (code "82") (name "unconnected-(WIFI-PadGPIO2)") (class "Default")
      (node (ref "WIFI") (pin "GPIO2") (pinfunction "GPIO2_GPIO2") (pintype "bidirectional"))
    )
    (net (code "83") (name "unconnected-(WIFI-PadRST)") (class "Default")
      (node (ref "WIFI") (pin "RST") (pinfunction "RST_RST") (pintype "bidirectional"))
    )
  )
)
